# therm-coast.net
KiCad netlist of a schematic drawn in EAGLE
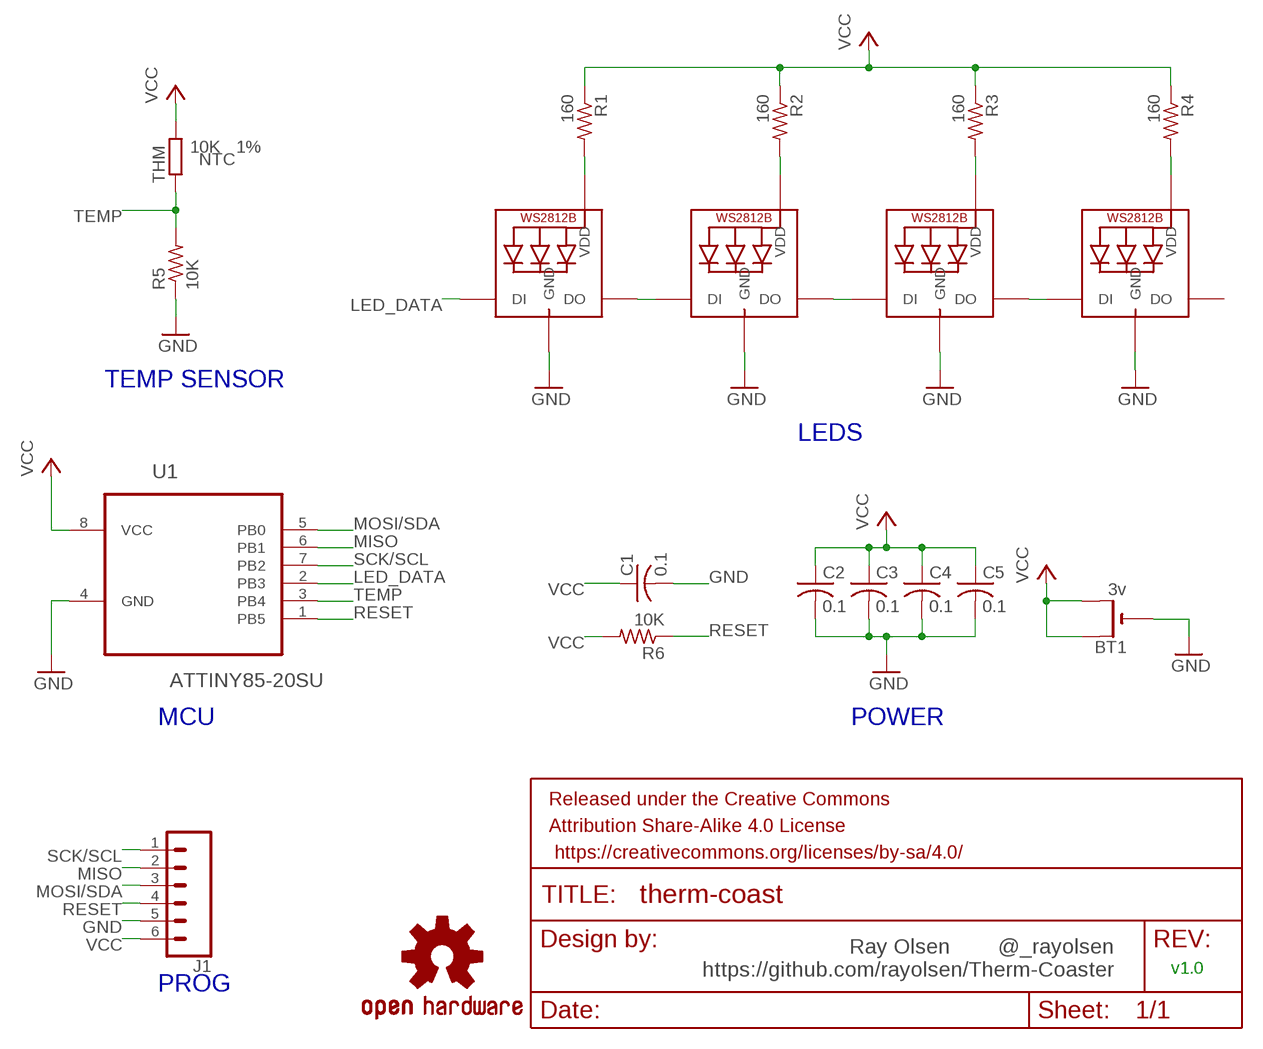
[diagram p0: schematic, sheet 1]

(export (version "E")
  (design (tool "Eeschema 10.0.6"))
  (components
    (comp (ref "BT1")
      (value "3v")
      (footprint "eagle-import:CR2032-SMD")
      (libsource (lib "eagle-import") (part "CR2032SMT"))
    )
    (comp (ref "C1")
      (value "0.1")
      (footprint "eagle-import:C0805")
      (libsource (lib "eagle-import") (part "C-USC0805"))
    )
    (comp (ref "C2")
      (value "0.1")
      (footprint "eagle-import:C0805")
      (libsource (lib "eagle-import") (part "C-USC0805"))
    )
    (comp (ref "C3")
      (value "0.1")
      (footprint "eagle-import:C0805")
      (libsource (lib "eagle-import") (part "C-USC0805"))
    )
    (comp (ref "C4")
      (value "0.1")
      (footprint "eagle-import:C0805")
      (libsource (lib "eagle-import") (part "C-USC0805"))
    )
    (comp (ref "C5")
      (value "0.1")
      (footprint "eagle-import:C0805")
      (libsource (lib "eagle-import") (part "C-USC0805"))
    )
    (comp (ref "FRAME1")
      (value "FRAME-LETTER")
      (footprint "eagle-import:CREATIVE_COMMONS")
      (libsource (lib "eagle-import") (part "FRAME-LETTER"))
    )
    (comp (ref "J1")
      (value "CONN_06SMD-FEMALE-V2")
      (footprint "eagle-import:1X06-SMD-FEMALE")
      (libsource (lib "eagle-import") (part "CONN_06SMD-FEMALE-V2"))
    )
    (comp (ref "LED1")
      (value "WS2812B5050")
      (footprint "eagle-import:WS2812B")
      (libsource (lib "eagle-import") (part "WS2812B5050"))
    )
    (comp (ref "LED2")
      (value "WS2812B5050")
      (footprint "eagle-import:WS2812B")
      (libsource (lib "eagle-import") (part "WS2812B5050"))
    )
    (comp (ref "LED3")
      (value "WS2812B5050")
      (footprint "eagle-import:WS2812B")
      (libsource (lib "eagle-import") (part "WS2812B5050"))
    )
    (comp (ref "LED4")
      (value "WS2812B5050")
      (footprint "eagle-import:WS2812B")
      (libsource (lib "eagle-import") (part "WS2812B5050"))
    )
    (comp (ref "LOGO1")
      (value "OSHW-LOGOL")
      (footprint "eagle-import:OSHW-LOGO-L")
      (libsource (lib "eagle-import") (part "OSHW-LOGOL"))
    )
    (comp (ref "R1")
      (value "160")
      (footprint "eagle-import:R0805")
      (libsource (lib "eagle-import") (part "R-US_R0805"))
    )
    (comp (ref "R2")
      (value "160")
      (footprint "eagle-import:R0805")
      (libsource (lib "eagle-import") (part "R-US_R0805"))
    )
    (comp (ref "R3")
      (value "160")
      (footprint "eagle-import:R0805")
      (libsource (lib "eagle-import") (part "R-US_R0805"))
    )
    (comp (ref "R4")
      (value "160")
      (footprint "eagle-import:R0805")
      (libsource (lib "eagle-import") (part "R-US_R0805"))
    )
    (comp (ref "R5")
      (value "10K")
      (footprint "eagle-import:R0805")
      (libsource (lib "eagle-import") (part "R-US_R0805"))
    )
    (comp (ref "R6")
      (value "10K")
      (footprint "eagle-import:R0805")
      (libsource (lib "eagle-import") (part "R-US_R0805"))
    )
    (comp (ref "THM")
      (value "10K")
      (footprint "eagle-import:R0805")
      (fields (field (name "TOLERANCE") "1%") (field (name "TYPE") "NTC"))
      (libsource (lib "eagle-import") (part "R-EU_R0805"))
    )
    (comp (ref "U1")
      (value "ATTINY85-20SU")
      (footprint "eagle-import:SOIC127P798X216-8N")
      (libsource (lib "eagle-import") (part "ATTINY85-20SU"))
    )
  )
  (nets
    (net (code "1") (name "/LED_DATA") (class "Default")
      (node (ref "LED1") (pin "4-DIN") (pinfunction "DI_4-DIN") (pintype "input"))
      (node (ref "U1") (pin "2") (pinfunction "PB3_2") (pintype "bidirectional"))
    )
    (net (code "2") (name "/MISO") (class "Default")
      (node (ref "J1") (pin "2") (pinfunction "2_2") (pintype "passive"))
      (node (ref "U1") (pin "6") (pinfunction "PB1_6") (pintype "bidirectional"))
    )
    (net (code "3") (name "/MOSI{slash}SDA") (class "Default")
      (node (ref "J1") (pin "3") (pinfunction "3_3") (pintype "passive"))
      (node (ref "U1") (pin "5") (pinfunction "PB0_5") (pintype "bidirectional"))
    )
    (net (code "4") (name "/RESET") (class "Default")
      (node (ref "J1") (pin "4") (pinfunction "4_4") (pintype "passive"))
      (node (ref "R6") (pin "1") (pinfunction "1_1") (pintype "passive"))
      (node (ref "U1") (pin "1") (pinfunction "PB5_1") (pintype "bidirectional"))
    )
    (net (code "5") (name "/SCK{slash}SCL") (class "Default")
      (node (ref "J1") (pin "1") (pinfunction "1_1") (pintype "passive"))
      (node (ref "U1") (pin "7") (pinfunction "PB2_7") (pintype "bidirectional"))
    )
    (net (code "6") (name "/TEMP") (class "Default")
      (node (ref "R5") (pin "2") (pinfunction "2_2") (pintype "passive"))
      (node (ref "THM") (pin "1") (pinfunction "1_1") (pintype "passive"))
      (node (ref "U1") (pin "3") (pinfunction "PB4_3") (pintype "bidirectional"))
    )
    (net (code "7") (name "GND") (class "Default")
      (node (ref "BT1") (pin "-") (pinfunction "-_-") (pintype "passive"))
      (node (ref "C1") (pin "2") (pinfunction "2_2") (pintype "passive"))
      (node (ref "C2") (pin "2") (pinfunction "2_2") (pintype "passive"))
      (node (ref "C3") (pin "2") (pinfunction "2_2") (pintype "passive"))
      (node (ref "C4") (pin "2") (pinfunction "2_2") (pintype "passive"))
      (node (ref "C5") (pin "2") (pinfunction "2_2") (pintype "passive"))
      (node (ref "J1") (pin "5") (pinfunction "5_5") (pintype "passive"))
      (node (ref "LED1") (pin "3-GND") (pinfunction "GND_3-GND") (pintype "power_in"))
      (node (ref "LED2") (pin "3-GND") (pinfunction "GND_3-GND") (pintype "power_in"))
      (node (ref "LED3") (pin "3-GND") (pinfunction "GND_3-GND") (pintype "power_in"))
      (node (ref "LED4") (pin "3-GND") (pinfunction "GND_3-GND") (pintype "power_in"))
      (node (ref "R5") (pin "1") (pinfunction "1_1") (pintype "passive"))
      (node (ref "U1") (pin "4") (pinfunction "GND_4") (pintype "passive"))
    )
    (net (code "8") (name "Net-(LED1-DO)") (class "Default")
      (node (ref "LED1") (pin "2-DOUT") (pinfunction "DO_2-DOUT") (pintype "output"))
      (node (ref "LED2") (pin "4-DIN") (pinfunction "DI_4-DIN") (pintype "input"))
    )
    (net (code "9") (name "Net-(LED1-VDD)") (class "Default")
      (node (ref "LED1") (pin "1-VDD") (pinfunction "VDD_1-VDD") (pintype "power_in"))
      (node (ref "R1") (pin "2") (pinfunction "2_2") (pintype "passive"))
    )
    (net (code "10") (name "Net-(LED2-DO)") (class "Default")
      (node (ref "LED2") (pin "2-DOUT") (pinfunction "DO_2-DOUT") (pintype "output"))
      (node (ref "LED3") (pin "4-DIN") (pinfunction "DI_4-DIN") (pintype "input"))
    )
    (net (code "11") (name "Net-(LED2-VDD)") (class "Default")
      (node (ref "LED2") (pin "1-VDD") (pinfunction "VDD_1-VDD") (pintype "power_in"))
      (node (ref "R2") (pin "2") (pinfunction "2_2") (pintype "passive"))
    )
    (net (code "12") (name "Net-(LED3-DO)") (class "Default")
      (node (ref "LED3") (pin "2-DOUT") (pinfunction "DO_2-DOUT") (pintype "output"))
      (node (ref "LED4") (pin "4-DIN") (pinfunction "DI_4-DIN") (pintype "input"))
    )
    (net (code "13") (name "Net-(LED3-VDD)") (class "Default")
      (node (ref "LED3") (pin "1-VDD") (pinfunction "VDD_1-VDD") (pintype "power_in"))
      (node (ref "R3") (pin "2") (pinfunction "2_2") (pintype "passive"))
    )
    (net (code "14") (name "Net-(LED4-VDD)") (class "Default")
      (node (ref "LED4") (pin "1-VDD") (pinfunction "VDD_1-VDD") (pintype "power_in"))
      (node (ref "R4") (pin "2") (pinfunction "2_2") (pintype "passive"))
    )
    (net (code "15") (name "VCC") (class "Default")
      (node (ref "BT1") (pin "+$1") (pinfunction "+_+$1") (pintype "passive"))
      (node (ref "BT1") (pin "+$2") (pinfunction "+1_+$2") (pintype "passive"))
      (node (ref "C1") (pin "1") (pinfunction "1_1") (pintype "passive"))
      (node (ref "C2") (pin "1") (pinfunction "1_1") (pintype "passive"))
      (node (ref "C3") (pin "1") (pinfunction "1_1") (pintype "passive"))
      (node (ref "C4") (pin "1") (pinfunction "1_1") (pintype "passive"))
      (node (ref "C5") (pin "1") (pinfunction "1_1") (pintype "passive"))
      (node (ref "J1") (pin "6") (pinfunction "6_6") (pintype "passive"))
      (node (ref "R1") (pin "1") (pinfunction "1_1") (pintype "passive"))
      (node (ref "R2") (pin "1") (pinfunction "1_1") (pintype "passive"))
      (node (ref "R3") (pin "1") (pinfunction "1_1") (pintype "passive"))
      (node (ref "R4") (pin "1") (pinfunction "1_1") (pintype "passive"))
      (node (ref "R6") (pin "2") (pinfunction "2_2") (pintype "passive"))
      (node (ref "THM") (pin "2") (pinfunction "2_2") (pintype "passive"))
      (node (ref "U1") (pin "8") (pinfunction "VCC_8") (pintype "power_in"))
    )
    (net (code "16") (name "unconnected-(LED4-DO-Pad2-DOUT)") (class "Default")
      (node (ref "LED4") (pin "2-DOUT") (pinfunction "DO_2-DOUT") (pintype "output"))
    )
  )
)
